# HB-UNI-SenAct-8-8-RC_V1_0.net
KiCad netlist of a schematic drawn in EAGLE
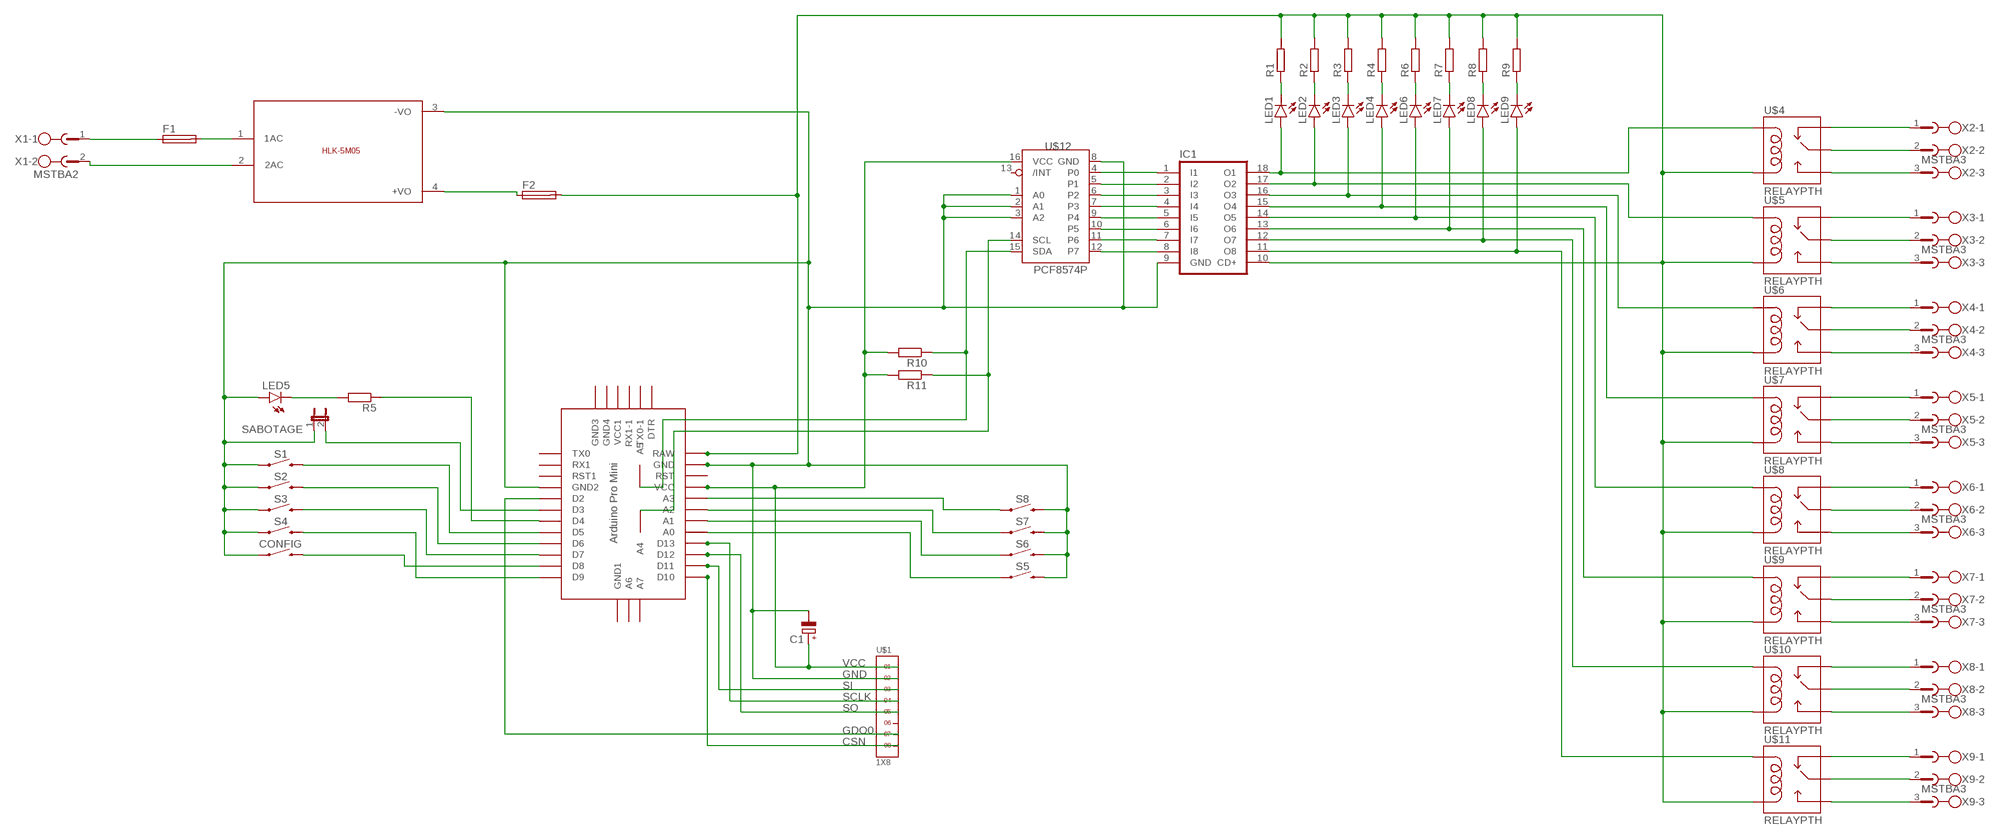
[diagram p0: schematic, sheet 1]

(export (version "E")
  (design (tool "Eeschema 10.0.6"))
  (components
    (comp (ref "C1")
      (value "CPOL-EUE2.5-5")
      (footprint "eagle-import:E2,5-5")
      (libsource (lib "eagle-import") (part "CPOL-EUE2.5-5"))
    )
    (comp (ref "CONFIG")
      (value "MOMENTARY-SWITCH-SPST-PTH-6.0MM-KIT")
      (footprint "eagle-import:TACTILE_SWITCH_PTH_6.0MM_KIT")
      (libsource (lib "eagle-import") (part "MOMENTARY-SWITCH-SPST-PTH-6.0MM-KIT"))
    )
    (comp (ref "F1")
      (value "SH22,5A")
      (footprint "eagle-import:SH22,5A")
      (fields (field (name "MPN") "0031.7701.11"))
      (libsource (lib "eagle-import") (part "SH22,5A"))
    )
    (comp (ref "F2")
      (value "SH22,5A")
      (footprint "eagle-import:SH22,5A")
      (fields (field (name "MPN") "0031.7701.11"))
      (libsource (lib "eagle-import") (part "SH22,5A"))
    )
    (comp (ref "IC1")
      (value "ULN2803A")
      (footprint "eagle-import:DIL18")
      (libsource (lib "eagle-import") (part "ULN2803A"))
    )
    (comp (ref "LED1")
      (value "LED3MM")
      (footprint "eagle-import:LED3MM")
      (libsource (lib "eagle-import") (part "LED3MM"))
    )
    (comp (ref "LED2")
      (value "LED3MM")
      (footprint "eagle-import:LED3MM")
      (libsource (lib "eagle-import") (part "LED3MM"))
    )
    (comp (ref "LED3")
      (value "LED3MM")
      (footprint "eagle-import:LED3MM")
      (libsource (lib "eagle-import") (part "LED3MM"))
    )
    (comp (ref "LED4")
      (value "LED3MM")
      (footprint "eagle-import:LED3MM")
      (libsource (lib "eagle-import") (part "LED3MM"))
    )
    (comp (ref "LED5")
      (value "LED3MM")
      (footprint "eagle-import:LED3MM")
      (libsource (lib "eagle-import") (part "LED3MM"))
    )
    (comp (ref "LED6")
      (value "LED3MM")
      (footprint "eagle-import:LED3MM")
      (libsource (lib "eagle-import") (part "LED3MM"))
    )
    (comp (ref "LED7")
      (value "LED3MM")
      (footprint "eagle-import:LED3MM")
      (libsource (lib "eagle-import") (part "LED3MM"))
    )
    (comp (ref "LED8")
      (value "LED3MM")
      (footprint "eagle-import:LED3MM")
      (libsource (lib "eagle-import") (part "LED3MM"))
    )
    (comp (ref "LED9")
      (value "LED3MM")
      (footprint "eagle-import:LED3MM")
      (libsource (lib "eagle-import") (part "LED3MM"))
    )
    (comp (ref "R1")
      (value "R-EU_0309/10")
      (footprint "eagle-import:0309_10")
      (libsource (lib "eagle-import") (part "R-EU_0309/10"))
    )
    (comp (ref "R2")
      (value "R-EU_0309/10")
      (footprint "eagle-import:0309_10")
      (libsource (lib "eagle-import") (part "R-EU_0309/10"))
    )
    (comp (ref "R3")
      (value "R-EU_0309/10")
      (footprint "eagle-import:0309_10")
      (libsource (lib "eagle-import") (part "R-EU_0309/10"))
    )
    (comp (ref "R4")
      (value "R-EU_0309/10")
      (footprint "eagle-import:0309_10")
      (libsource (lib "eagle-import") (part "R-EU_0309/10"))
    )
    (comp (ref "R5")
      (value "R-EU_0309/10")
      (footprint "eagle-import:0309_10")
      (libsource (lib "eagle-import") (part "R-EU_0309/10"))
    )
    (comp (ref "R6")
      (value "R-EU_0309/10")
      (footprint "eagle-import:0309_10")
      (libsource (lib "eagle-import") (part "R-EU_0309/10"))
    )
    (comp (ref "R7")
      (value "R-EU_0309/10")
      (footprint "eagle-import:0309_10")
      (libsource (lib "eagle-import") (part "R-EU_0309/10"))
    )
    (comp (ref "R8")
      (value "R-EU_0309/10")
      (footprint "eagle-import:0309_10")
      (libsource (lib "eagle-import") (part "R-EU_0309/10"))
    )
    (comp (ref "R9")
      (value "R-EU_0309/10")
      (footprint "eagle-import:0309_10")
      (libsource (lib "eagle-import") (part "R-EU_0309/10"))
    )
    (comp (ref "R10")
      (value "R-EU_0309/10")
      (footprint "eagle-import:0309_10")
      (libsource (lib "eagle-import") (part "R-EU_0309/10"))
    )
    (comp (ref "R11")
      (value "R-EU_0309/10")
      (footprint "eagle-import:0309_10")
      (libsource (lib "eagle-import") (part "R-EU_0309/10"))
    )
    (comp (ref "S1")
      (value "MOMENTARY-SWITCH-SPST-PTH-6.0MM")
      (footprint "eagle-import:TACTILE_SWITCH_PTH_6.0MM")
      (libsource (lib "eagle-import") (part "MOMENTARY-SWITCH-SPST-PTH-6.0MM"))
    )
    (comp (ref "S2")
      (value "MOMENTARY-SWITCH-SPST-PTH-6.0MM-KIT")
      (footprint "eagle-import:TACTILE_SWITCH_PTH_6.0MM_KIT")
      (libsource (lib "eagle-import") (part "MOMENTARY-SWITCH-SPST-PTH-6.0MM-KIT"))
    )
    (comp (ref "S3")
      (value "MOMENTARY-SWITCH-SPST-PTH-6.0MM-KIT")
      (footprint "eagle-import:TACTILE_SWITCH_PTH_6.0MM_KIT")
      (libsource (lib "eagle-import") (part "MOMENTARY-SWITCH-SPST-PTH-6.0MM-KIT"))
    )
    (comp (ref "S4")
      (value "MOMENTARY-SWITCH-SPST-PTH-6.0MM-KIT")
      (footprint "eagle-import:TACTILE_SWITCH_PTH_6.0MM_KIT")
      (libsource (lib "eagle-import") (part "MOMENTARY-SWITCH-SPST-PTH-6.0MM-KIT"))
    )
    (comp (ref "S5")
      (value "MOMENTARY-SWITCH-SPST-PTH-6.0MM-KIT")
      (footprint "eagle-import:TACTILE_SWITCH_PTH_6.0MM_KIT")
      (libsource (lib "eagle-import") (part "MOMENTARY-SWITCH-SPST-PTH-6.0MM-KIT"))
    )
    (comp (ref "S6")
      (value "MOMENTARY-SWITCH-SPST-PTH-6.0MM-KIT")
      (footprint "eagle-import:TACTILE_SWITCH_PTH_6.0MM_KIT")
      (libsource (lib "eagle-import") (part "MOMENTARY-SWITCH-SPST-PTH-6.0MM-KIT"))
    )
    (comp (ref "S7")
      (value "MOMENTARY-SWITCH-SPST-PTH-6.0MM-KIT")
      (footprint "eagle-import:TACTILE_SWITCH_PTH_6.0MM_KIT")
      (libsource (lib "eagle-import") (part "MOMENTARY-SWITCH-SPST-PTH-6.0MM-KIT"))
    )
    (comp (ref "S8")
      (value "MOMENTARY-SWITCH-SPST-PTH-6.0MM-KIT")
      (footprint "eagle-import:TACTILE_SWITCH_PTH_6.0MM_KIT")
      (libsource (lib "eagle-import") (part "MOMENTARY-SWITCH-SPST-PTH-6.0MM-KIT"))
    )
    (comp (ref "SABOTAGE")
      (value "JP1E")
      (footprint "eagle-import:JP1")
      (libsource (lib "eagle-import") (part "JP1E"))
    )
    (comp (ref "U$1")
      (value "1X8")
      (footprint "eagle-import:1X8")
      (libsource (lib "eagle-import") (part "1X8"))
    )
    (comp (ref "U$2")
      (value "ABK-PRO-MINI")
      (footprint "eagle-import:ABK-PRO-MINI")
      (libsource (lib "eagle-import") (part "ABK-PRO-MINI"))
    )
    (comp (ref "U$3")
      (value "5VDC/5W")
      (footprint "eagle-import:HLK-5M05")
      (libsource (lib "eagle-import") (part "HLK-5M05"))
    )
    (comp (ref "U$4")
      (value "RELAYPTH")
      (footprint "eagle-import:SRD-05VDC-SL-C")
      (libsource (lib "eagle-import") (part "RELAYPTH"))
    )
    (comp (ref "U$5")
      (value "RELAYPTH")
      (footprint "eagle-import:SRD-05VDC-SL-C")
      (libsource (lib "eagle-import") (part "RELAYPTH"))
    )
    (comp (ref "U$6")
      (value "RELAYPTH")
      (footprint "eagle-import:SRD-05VDC-SL-C")
      (libsource (lib "eagle-import") (part "RELAYPTH"))
    )
    (comp (ref "U$7")
      (value "RELAYPTH")
      (footprint "eagle-import:SRD-05VDC-SL-C")
      (libsource (lib "eagle-import") (part "RELAYPTH"))
    )
    (comp (ref "U$8")
      (value "RELAYPTH")
      (footprint "eagle-import:SRD-05VDC-SL-C")
      (libsource (lib "eagle-import") (part "RELAYPTH"))
    )
    (comp (ref "U$9")
      (value "RELAYPTH")
      (footprint "eagle-import:SRD-05VDC-SL-C")
      (libsource (lib "eagle-import") (part "RELAYPTH"))
    )
    (comp (ref "U$10")
      (value "RELAYPTH")
      (footprint "eagle-import:SRD-05VDC-SL-C")
      (libsource (lib "eagle-import") (part "RELAYPTH"))
    )
    (comp (ref "U$11")
      (value "RELAYPTH")
      (footprint "eagle-import:SRD-05VDC-SL-C")
      (libsource (lib "eagle-import") (part "RELAYPTH"))
    )
    (comp (ref "U$12")
      (value "PCF8574P")
      (footprint "eagle-import:DIL16")
      (libsource (lib "eagle-import") (part "PCF8574P"))
    )
    (comp (ref "X1")
      (value "MSTBA2")
      (footprint "eagle-import:MSTBA2")
      (fields (field (name "MF") "FARNELL") (field (name "MPN") "1757242"))
      (libsource (lib "eagle-import") (part "MSTBA2"))
    )
    (comp (ref "X2")
      (value "MSTBA3")
      (footprint "eagle-import:MSTBA3")
      (fields (field (name "MF") "FARNELL") (field (name "MPN") "1757255"))
      (libsource (lib "eagle-import") (part "MSTBA3"))
    )
    (comp (ref "X3")
      (value "MSTBA3")
      (footprint "eagle-import:MSTBA3")
      (fields (field (name "MF") "FARNELL") (field (name "MPN") "1757255"))
      (libsource (lib "eagle-import") (part "MSTBA3"))
    )
    (comp (ref "X4")
      (value "MSTBA3")
      (footprint "eagle-import:MSTBA3")
      (fields (field (name "MF") "FARNELL") (field (name "MPN") "1757255"))
      (libsource (lib "eagle-import") (part "MSTBA3"))
    )
    (comp (ref "X5")
      (value "MSTBA3")
      (footprint "eagle-import:MSTBA3")
      (fields (field (name "MF") "FARNELL") (field (name "MPN") "1757255"))
      (libsource (lib "eagle-import") (part "MSTBA3"))
    )
    (comp (ref "X6")
      (value "MSTBA3")
      (footprint "eagle-import:MSTBA3")
      (fields (field (name "MF") "FARNELL") (field (name "MPN") "1757255"))
      (libsource (lib "eagle-import") (part "MSTBA3"))
    )
    (comp (ref "X7")
      (value "MSTBA3")
      (footprint "eagle-import:MSTBA3")
      (fields (field (name "MF") "FARNELL") (field (name "MPN") "1757255"))
      (libsource (lib "eagle-import") (part "MSTBA3"))
    )
    (comp (ref "X8")
      (value "MSTBA3")
      (footprint "eagle-import:MSTBA3")
      (fields (field (name "MF") "FARNELL") (field (name "MPN") "1757255"))
      (libsource (lib "eagle-import") (part "MSTBA3"))
    )
    (comp (ref "X9")
      (value "MSTBA3")
      (footprint "eagle-import:MSTBA3")
      (fields (field (name "MF") "FARNELL") (field (name "MPN") "1757255"))
      (libsource (lib "eagle-import") (part "MSTBA3"))
    )
  )
  (nets
    (net (code "1") (name "/CSN") (class "Default")
      (node (ref "U$1") (pin "8") (pinfunction "8_8") (pintype "bidirectional"))
      (node (ref "U$2") (pin "D10") (pinfunction "D10_D10") (pintype "bidirectional"))
    )
    (net (code "2") (name "/GDO0") (class "Default")
      (node (ref "U$1") (pin "7") (pinfunction "7_7") (pintype "bidirectional"))
      (node (ref "U$2") (pin "D2") (pinfunction "D2_D2") (pintype "bidirectional"))
    )
    (net (code "3") (name "/GND") (class "Default")
      (node (ref "C1") (pin "-") (pinfunction "-_-") (pintype "passive"))
      (node (ref "CONFIG") (pin "1") (pinfunction "1_1") (pintype "passive"))
      (node (ref "IC1") (pin "9") (pinfunction "GND_9") (pintype "power_in"))
      (node (ref "LED5") (pin "A") (pinfunction "A_A") (pintype "passive"))
      (node (ref "S1") (pin "1") (pinfunction "1_1") (pintype "passive"))
      (node (ref "S2") (pin "1") (pinfunction "1_1") (pintype "passive"))
      (node (ref "S3") (pin "1") (pinfunction "1_1") (pintype "passive"))
      (node (ref "S4") (pin "1") (pinfunction "1_1") (pintype "passive"))
      (node (ref "S5") (pin "3") (pinfunction "2_3") (pintype "passive"))
      (node (ref "S6") (pin "3") (pinfunction "2_3") (pintype "passive"))
      (node (ref "S7") (pin "3") (pinfunction "2_3") (pintype "passive"))
      (node (ref "S8") (pin "3") (pinfunction "2_3") (pintype "passive"))
      (node (ref "SABOTAGE") (pin "1") (pinfunction "1_1") (pintype "passive"))
      (node (ref "U$1") (pin "2") (pinfunction "2_2") (pintype "bidirectional"))
      (node (ref "U$12") (pin "1") (pinfunction "A0_1") (pintype "input"))
      (node (ref "U$12") (pin "2") (pinfunction "A1_2") (pintype "input"))
      (node (ref "U$12") (pin "3") (pinfunction "A2_3") (pintype "input"))
      (node (ref "U$12") (pin "8") (pinfunction "GND_8") (pintype "power_in"))
      (node (ref "U$2") (pin "GND") (pinfunction "GND_GND") (pintype "bidirectional"))
      (node (ref "U$2") (pin "GND1") (pinfunction "GND2_GND1") (pintype "bidirectional"))
      (node (ref "U$3") (pin "3") (pinfunction "-VO_3") (pintype "bidirectional"))
    )
    (net (code "4") (name "/SCLK") (class "Default")
      (node (ref "U$1") (pin "4") (pinfunction "4_4") (pintype "bidirectional"))
      (node (ref "U$2") (pin "D13") (pinfunction "D13_D13") (pintype "bidirectional"))
    )
    (net (code "5") (name "/SI") (class "Default")
      (node (ref "U$1") (pin "3") (pinfunction "3_3") (pintype "bidirectional"))
      (node (ref "U$2") (pin "D11") (pinfunction "D11_D11") (pintype "bidirectional"))
    )
    (net (code "6") (name "/SO") (class "Default")
      (node (ref "U$1") (pin "5") (pinfunction "5_5") (pintype "bidirectional"))
      (node (ref "U$2") (pin "D12") (pinfunction "D12_D12") (pintype "bidirectional"))
    )
    (net (code "7") (name "/VCC") (class "Default")
      (node (ref "C1") (pin "+") (pinfunction "+_+") (pintype "passive"))
      (node (ref "R10") (pin "2") (pinfunction "2_2") (pintype "passive"))
      (node (ref "R11") (pin "2") (pinfunction "2_2") (pintype "passive"))
      (node (ref "U$1") (pin "1") (pinfunction "1_1") (pintype "bidirectional"))
      (node (ref "U$12") (pin "16") (pinfunction "VCC_16") (pintype "power_in"))
      (node (ref "U$2") (pin "VCC") (pinfunction "VCC_VCC") (pintype "bidirectional"))
    )
    (net (code "8") (name "Net-(CONFIG-2)") (class "Default")
      (node (ref "CONFIG") (pin "3") (pinfunction "2_3") (pintype "passive"))
      (node (ref "U$2") (pin "D8") (pinfunction "D8_D8") (pintype "bidirectional"))
    )
    (net (code "9") (name "Net-(F1-Pad1)") (class "Default")
      (node (ref "F1") (pin "1") (pinfunction "1_1") (pintype "passive"))
      (node (ref "X1") (pin "1") (pinfunction "1_1") (pintype "passive"))
    )
    (net (code "10") (name "Net-(IC1-CD+)") (class "Default")
      (node (ref "F2") (pin "2") (pinfunction "2_2") (pintype "passive"))
      (node (ref "IC1") (pin "10") (pinfunction "CD+_10") (pintype "passive"))
      (node (ref "R1") (pin "2") (pinfunction "2_2") (pintype "passive"))
      (node (ref "R2") (pin "2") (pinfunction "2_2") (pintype "passive"))
      (node (ref "R3") (pin "2") (pinfunction "2_2") (pintype "passive"))
      (node (ref "R4") (pin "2") (pinfunction "2_2") (pintype "passive"))
      (node (ref "R6") (pin "2") (pinfunction "2_2") (pintype "passive"))
      (node (ref "R7") (pin "2") (pinfunction "2_2") (pintype "passive"))
      (node (ref "R8") (pin "2") (pinfunction "2_2") (pintype "passive"))
      (node (ref "R9") (pin "2") (pinfunction "2_2") (pintype "passive"))
      (node (ref "U$10") (pin "COIL0") (pinfunction "COIL0_COIL0") (pintype "bidirectional"))
      (node (ref "U$11") (pin "COIL0") (pinfunction "COIL0_COIL0") (pintype "bidirectional"))
      (node (ref "U$2") (pin "RAW") (pinfunction "RAW_RAW") (pintype "bidirectional"))
      (node (ref "U$4") (pin "COIL0") (pinfunction "COIL0_COIL0") (pintype "bidirectional"))
      (node (ref "U$5") (pin "COIL0") (pinfunction "COIL0_COIL0") (pintype "bidirectional"))
      (node (ref "U$6") (pin "COIL0") (pinfunction "COIL0_COIL0") (pintype "bidirectional"))
      (node (ref "U$7") (pin "COIL0") (pinfunction "COIL0_COIL0") (pintype "bidirectional"))
      (node (ref "U$8") (pin "COIL0") (pinfunction "COIL0_COIL0") (pintype "bidirectional"))
      (node (ref "U$9") (pin "COIL0") (pinfunction "COIL0_COIL0") (pintype "bidirectional"))
    )
    (net (code "11") (name "Net-(IC1-I1)") (class "Default")
      (node (ref "IC1") (pin "1") (pinfunction "I1_1") (pintype "input"))
      (node (ref "U$12") (pin "4") (pinfunction "P0_4") (pintype "bidirectional"))
    )
    (net (code "12") (name "Net-(IC1-I2)") (class "Default")
      (node (ref "IC1") (pin "2") (pinfunction "I2_2") (pintype "input"))
      (node (ref "U$12") (pin "5") (pinfunction "P1_5") (pintype "bidirectional"))
    )
    (net (code "13") (name "Net-(IC1-I3)") (class "Default")
      (node (ref "IC1") (pin "3") (pinfunction "I3_3") (pintype "input"))
      (node (ref "U$12") (pin "6") (pinfunction "P2_6") (pintype "bidirectional"))
    )
    (net (code "14") (name "Net-(IC1-I4)") (class "Default")
      (node (ref "IC1") (pin "4") (pinfunction "I4_4") (pintype "input"))
      (node (ref "U$12") (pin "7") (pinfunction "P3_7") (pintype "bidirectional"))
    )
    (net (code "15") (name "Net-(IC1-I5)") (class "Default")
      (node (ref "IC1") (pin "5") (pinfunction "I5_5") (pintype "input"))
      (node (ref "U$12") (pin "9") (pinfunction "P4_9") (pintype "bidirectional"))
    )
    (net (code "16") (name "Net-(IC1-I6)") (class "Default")
      (node (ref "IC1") (pin "6") (pinfunction "I6_6") (pintype "input"))
      (node (ref "U$12") (pin "10") (pinfunction "P5_10") (pintype "bidirectional"))
    )
    (net (code "17") (name "Net-(IC1-I7)") (class "Default")
      (node (ref "IC1") (pin "7") (pinfunction "I7_7") (pintype "input"))
      (node (ref "U$12") (pin "11") (pinfunction "P6_11") (pintype "bidirectional"))
    )
    (net (code "18") (name "Net-(IC1-I8)") (class "Default")
      (node (ref "IC1") (pin "8") (pinfunction "I8_8") (pintype "input"))
      (node (ref "U$12") (pin "12") (pinfunction "P7_12") (pintype "bidirectional"))
    )
    (net (code "19") (name "Net-(IC1-O1)") (class "Default")
      (node (ref "IC1") (pin "18") (pinfunction "O1_18") (pintype "open_collector"))
      (node (ref "LED1") (pin "A") (pinfunction "A_A") (pintype "passive"))
      (node (ref "U$4") (pin "COIL1") (pinfunction "COIL1_COIL1") (pintype "bidirectional"))
    )
    (net (code "20") (name "Net-(IC1-O2)") (class "Default")
      (node (ref "IC1") (pin "17") (pinfunction "O2_17") (pintype "open_collector"))
      (node (ref "LED2") (pin "A") (pinfunction "A_A") (pintype "passive"))
      (node (ref "U$5") (pin "COIL1") (pinfunction "COIL1_COIL1") (pintype "bidirectional"))
    )
    (net (code "21") (name "Net-(IC1-O3)") (class "Default")
      (node (ref "IC1") (pin "16") (pinfunction "O3_16") (pintype "open_collector"))
      (node (ref "LED3") (pin "A") (pinfunction "A_A") (pintype "passive"))
      (node (ref "U$6") (pin "COIL1") (pinfunction "COIL1_COIL1") (pintype "bidirectional"))
    )
    (net (code "22") (name "Net-(IC1-O4)") (class "Default")
      (node (ref "IC1") (pin "15") (pinfunction "O4_15") (pintype "open_collector"))
      (node (ref "LED4") (pin "A") (pinfunction "A_A") (pintype "passive"))
      (node (ref "U$7") (pin "COIL1") (pinfunction "COIL1_COIL1") (pintype "bidirectional"))
    )
    (net (code "23") (name "Net-(IC1-O5)") (class "Default")
      (node (ref "IC1") (pin "14") (pinfunction "O5_14") (pintype "open_collector"))
      (node (ref "LED6") (pin "A") (pinfunction "A_A") (pintype "passive"))
      (node (ref "U$8") (pin "COIL1") (pinfunction "COIL1_COIL1") (pintype "bidirectional"))
    )
    (net (code "24") (name "Net-(IC1-O6)") (class "Default")
      (node (ref "IC1") (pin "13") (pinfunction "O6_13") (pintype "open_collector"))
      (node (ref "LED7") (pin "A") (pinfunction "A_A") (pintype "passive"))
      (node (ref "U$9") (pin "COIL1") (pinfunction "COIL1_COIL1") (pintype "bidirectional"))
    )
    (net (code "25") (name "Net-(IC1-O7)") (class "Default")
      (node (ref "IC1") (pin "12") (pinfunction "O7_12") (pintype "open_collector"))
      (node (ref "LED8") (pin "A") (pinfunction "A_A") (pintype "passive"))
      (node (ref "U$10") (pin "COIL1") (pinfunction "COIL1_COIL1") (pintype "bidirectional"))
    )
    (net (code "26") (name "Net-(IC1-O8)") (class "Default")
      (node (ref "IC1") (pin "11") (pinfunction "O8_11") (pintype "open_collector"))
      (node (ref "LED9") (pin "A") (pinfunction "A_A") (pintype "passive"))
      (node (ref "U$11") (pin "COIL1") (pinfunction "COIL1_COIL1") (pintype "bidirectional"))
    )
    (net (code "27") (name "Net-(LED1-C)") (class "Default")
      (node (ref "LED1") (pin "K") (pinfunction "C_K") (pintype "passive"))
      (node (ref "R1") (pin "1") (pinfunction "1_1") (pintype "passive"))
    )
    (net (code "28") (name "Net-(LED2-C)") (class "Default")
      (node (ref "LED2") (pin "K") (pinfunction "C_K") (pintype "passive"))
      (node (ref "R2") (pin "1") (pinfunction "1_1") (pintype "passive"))
    )
    (net (code "29") (name "Net-(LED3-C)") (class "Default")
      (node (ref "LED3") (pin "K") (pinfunction "C_K") (pintype "passive"))
      (node (ref "R3") (pin "1") (pinfunction "1_1") (pintype "passive"))
    )
    (net (code "30") (name "Net-(LED4-C)") (class "Default")
      (node (ref "LED4") (pin "K") (pinfunction "C_K") (pintype "passive"))
      (node (ref "R4") (pin "1") (pinfunction "1_1") (pintype "passive"))
    )
    (net (code "31") (name "Net-(LED5-C)") (class "Default")
      (node (ref "LED5") (pin "K") (pinfunction "C_K") (pintype "passive"))
      (node (ref "R5") (pin "2") (pinfunction "2_2") (pintype "passive"))
    )
    (net (code "32") (name "Net-(LED6-C)") (class "Default")
      (node (ref "LED6") (pin "K") (pinfunction "C_K") (pintype "passive"))
      (node (ref "R6") (pin "1") (pinfunction "1_1") (pintype "passive"))
    )
    (net (code "33") (name "Net-(LED7-C)") (class "Default")
      (node (ref "LED7") (pin "K") (pinfunction "C_K") (pintype "passive"))
      (node (ref "R7") (pin "1") (pinfunction "1_1") (pintype "passive"))
    )
    (net (code "34") (name "Net-(LED8-C)") (class "Default")
      (node (ref "LED8") (pin "K") (pinfunction "C_K") (pintype "passive"))
      (node (ref "R8") (pin "1") (pinfunction "1_1") (pintype "passive"))
    )
    (net (code "35") (name "Net-(LED9-C)") (class "Default")
      (node (ref "LED9") (pin "K") (pinfunction "C_K") (pintype "passive"))
      (node (ref "R9") (pin "1") (pinfunction "1_1") (pintype "passive"))
    )
    (net (code "36") (name "Net-(R5-Pad1)") (class "Default")
      (node (ref "R5") (pin "1") (pinfunction "1_1") (pintype "passive"))
      (node (ref "U$2") (pin "D4") (pinfunction "D4_D4") (pintype "bidirectional"))
    )
    (net (code "37") (name "Net-(S1-2)") (class "Default")
      (node (ref "S1") (pin "3") (pinfunction "2_3") (pintype "passive"))
      (node (ref "U$2") (pin "D5") (pinfunction "D5_D5") (pintype "bidirectional"))
    )
    (net (code "38") (name "Net-(S2-2)") (class "Default")
      (node (ref "S2") (pin "3") (pinfunction "2_3") (pintype "passive"))
      (node (ref "U$2") (pin "D6") (pinfunction "D6_D6") (pintype "bidirectional"))
    )
    (net (code "39") (name "Net-(S3-2)") (class "Default")
      (node (ref "S3") (pin "3") (pinfunction "2_3") (pintype "passive"))
      (node (ref "U$2") (pin "D7") (pinfunction "D7_D7") (pintype "bidirectional"))
    )
    (net (code "40") (name "Net-(S4-2)") (class "Default")
      (node (ref "S4") (pin "3") (pinfunction "2_3") (pintype "passive"))
      (node (ref "U$2") (pin "D9") (pinfunction "D9_D9") (pintype "bidirectional"))
    )
    (net (code "41") (name "Net-(S5-Pad1)") (class "Default")
      (node (ref "S5") (pin "1") (pinfunction "1_1") (pintype "passive"))
      (node (ref "U$2") (pin "A0") (pinfunction "A0_A0") (pintype "bidirectional"))
    )
    (net (code "42") (name "Net-(S6-Pad1)") (class "Default")
      (node (ref "S6") (pin "1") (pinfunction "1_1") (pintype "passive"))
      (node (ref "U$2") (pin "A1") (pinfunction "A1_A1") (pintype "bidirectional"))
    )
    (net (code "43") (name "Net-(S7-Pad1)") (class "Default")
      (node (ref "S7") (pin "1") (pinfunction "1_1") (pintype "passive"))
      (node (ref "U$2") (pin "A2") (pinfunction "A2_A2") (pintype "bidirectional"))
    )
    (net (code "44") (name "Net-(S8-Pad1)") (class "Default")
      (node (ref "S8") (pin "1") (pinfunction "1_1") (pintype "passive"))
      (node (ref "U$2") (pin "A3") (pinfunction "A3_A3") (pintype "bidirectional"))
    )
    (net (code "45") (name "Net-(SABOTAGE-Pad2)") (class "Default")
      (node (ref "SABOTAGE") (pin "2") (pinfunction "2_2") (pintype "passive"))
      (node (ref "U$2") (pin "D3") (pinfunction "D3_D3") (pintype "bidirectional"))
    )
    (net (code "46") (name "Net-(U$3-+VO)") (class "Default")
      (node (ref "F2") (pin "1") (pinfunction "1_1") (pintype "passive"))
      (node (ref "U$3") (pin "4") (pinfunction "+VO_4") (pintype "bidirectional"))
    )
    (net (code "47") (name "Net-(U$3-1AC)") (class "Default")
      (node (ref "F1") (pin "2") (pinfunction "2_2") (pintype "passive"))
      (node (ref "U$3") (pin "1") (pinfunction "1AC_1") (pintype "bidirectional"))
    )
    (net (code "48") (name "Net-(U$3-2AC)") (class "Default")
      (node (ref "U$3") (pin "2") (pinfunction "2AC_2") (pintype "bidirectional"))
      (node (ref "X1") (pin "2") (pinfunction "1_2") (pintype "passive"))
    )
    (net (code "49") (name "Net-(U$4-SWCLOSE)") (class "Default")
      (node (ref "U$4") (pin "SWCLOSED") (pinfunction "SWCLOSE_SWCLOSED") (pintype "bidirectional"))
      (node (ref "X2") (pin "1") (pinfunction "1_1") (pintype "passive"))
    )
    (net (code "50") (name "Net-(U$5-SWCLOSE)") (class "Default")
      (node (ref "U$5") (pin "SWCLOSED") (pinfunction "SWCLOSE_SWCLOSED") (pintype "bidirectional"))
      (node (ref "X3") (pin "1") (pinfunction "1_1") (pintype "passive"))
    )
    (net (code "51") (name "Net-(U$6-SWCLOSE)") (class "Default")
      (node (ref "U$6") (pin "SWCLOSED") (pinfunction "SWCLOSE_SWCLOSED") (pintype "bidirectional"))
      (node (ref "X4") (pin "1") (pinfunction "1_1") (pintype "passive"))
    )
    (net (code "52") (name "Net-(U$7-SWCLOSE)") (class "Default")
      (node (ref "U$7") (pin "SWCLOSED") (pinfunction "SWCLOSE_SWCLOSED") (pintype "bidirectional"))
      (node (ref "X5") (pin "1") (pinfunction "1_1") (pintype "passive"))
    )
    (net (code "53") (name "Net-(U$8-SWCLOSE)") (class "Default")
      (node (ref "U$8") (pin "SWCLOSED") (pinfunction "SWCLOSE_SWCLOSED") (pintype "bidirectional"))
      (node (ref "X6") (pin "1") (pinfunction "1_1") (pintype "passive"))
    )
    (net (code "54") (name "Net-(U$9-SWCLOSE)") (class "Default")
      (node (ref "U$9") (pin "SWCLOSED") (pinfunction "SWCLOSE_SWCLOSED") (pintype "bidirectional"))
      (node (ref "X7") (pin "1") (pinfunction "1_1") (pintype "passive"))
    )
    (net (code "55") (name "Net-(U$10-SWCLOSE)") (class "Default")
      (node (ref "U$10") (pin "SWCLOSED") (pinfunction "SWCLOSE_SWCLOSED") (pintype "bidirectional"))
      (node (ref "X8") (pin "1") (pinfunction "1_1") (pintype "passive"))
    )
    (net (code "56") (name "Net-(U$11-SWCLOSE)") (class "Default")
      (node (ref "U$11") (pin "SWCLOSED") (pinfunction "SWCLOSE_SWCLOSED") (pintype "bidirectional"))
      (node (ref "X9") (pin "1") (pinfunction "1_1") (pintype "passive"))
    )
    (net (code "57") (name "Net-(U$12-SCL)") (class "Default")
      (node (ref "R11") (pin "1") (pinfunction "1_1") (pintype "passive"))
      (node (ref "U$12") (pin "14") (pinfunction "SCL_14") (pintype "input"))
      (node (ref "U$2") (pin "A4") (pinfunction "A4_A4") (pintype "bidirectional"))
    )
    (net (code "58") (name "Net-(U$12-SDA)") (class "Default")
      (node (ref "R10") (pin "1") (pinfunction "1_1") (pintype "passive"))
      (node (ref "U$12") (pin "15") (pinfunction "SDA_15") (pintype "bidirectional"))
      (node (ref "U$2") (pin "A5") (pinfunction "A5_A5") (pintype "bidirectional"))
    )
    (net (code "59") (name "Net-(X2B-1)") (class "Default")
      (node (ref "U$4") (pin "SWCOMMON") (pinfunction "SWCOMMON_SWCOMMON") (pintype "bidirectional"))
      (node (ref "X2") (pin "2") (pinfunction "1_2") (pintype "passive"))
    )
    (net (code "60") (name "Net-(X2C-1)") (class "Default")
      (node (ref "U$4") (pin "SWOPEN") (pinfunction "SWOPEN_SWOPEN") (pintype "bidirectional"))
      (node (ref "X2") (pin "3") (pinfunction "1_3") (pintype "passive"))
    )
    (net (code "61") (name "Net-(X3B-1)") (class "Default")
      (node (ref "U$5") (pin "SWCOMMON") (pinfunction "SWCOMMON_SWCOMMON") (pintype "bidirectional"))
      (node (ref "X3") (pin "2") (pinfunction "1_2") (pintype "passive"))
    )
    (net (code "62") (name "Net-(X3C-1)") (class "Default")
      (node (ref "U$5") (pin "SWOPEN") (pinfunction "SWOPEN_SWOPEN") (pintype "bidirectional"))
      (node (ref "X3") (pin "3") (pinfunction "1_3") (pintype "passive"))
    )
    (net (code "63") (name "Net-(X4B-1)") (class "Default")
      (node (ref "U$6") (pin "SWCOMMON") (pinfunction "SWCOMMON_SWCOMMON") (pintype "bidirectional"))
      (node (ref "X4") (pin "2") (pinfunction "1_2") (pintype "passive"))
    )
    (net (code "64") (name "Net-(X4C-1)") (class "Default")
      (node (ref "U$6") (pin "SWOPEN") (pinfunction "SWOPEN_SWOPEN") (pintype "bidirectional"))
      (node (ref "X4") (pin "3") (pinfunction "1_3") (pintype "passive"))
    )
    (net (code "65") (name "Net-(X5B-1)") (class "Default")
      (node (ref "U$7") (pin "SWCOMMON") (pinfunction "SWCOMMON_SWCOMMON") (pintype "bidirectional"))
      (node (ref "X5") (pin "2") (pinfunction "1_2") (pintype "passive"))
    )
    (net (code "66") (name "Net-(X5C-1)") (class "Default")
      (node (ref "U$7") (pin "SWOPEN") (pinfunction "SWOPEN_SWOPEN") (pintype "bidirectional"))
      (node (ref "X5") (pin "3") (pinfunction "1_3") (pintype "passive"))
    )
    (net (code "67") (name "Net-(X6B-1)") (class "Default")
      (node (ref "U$8") (pin "SWCOMMON") (pinfunction "SWCOMMON_SWCOMMON") (pintype "bidirectional"))
      (node (ref "X6") (pin "2") (pinfunction "1_2") (pintype "passive"))
    )
    (net (code "68") (name "Net-(X6C-1)") (class "Default")
      (node (ref "U$8") (pin "SWOPEN") (pinfunction "SWOPEN_SWOPEN") (pintype "bidirectional"))
      (node (ref "X6") (pin "3") (pinfunction "1_3") (pintype "passive"))
    )
    (net (code "69") (name "Net-(X7B-1)") (class "Default")
      (node (ref "U$9") (pin "SWCOMMON") (pinfunction "SWCOMMON_SWCOMMON") (pintype "bidirectional"))
      (node (ref "X7") (pin "2") (pinfunction "1_2") (pintype "passive"))
    )
    (net (code "70") (name "Net-(X7C-1)") (class "Default")
      (node (ref "U$9") (pin "SWOPEN") (pinfunction "SWOPEN_SWOPEN") (pintype "bidirectional"))
      (node (ref "X7") (pin "3") (pinfunction "1_3") (pintype "passive"))
    )
    (net (code "71") (name "Net-(X8B-1)") (class "Default")
      (node (ref "U$10") (pin "SWCOMMON") (pinfunction "SWCOMMON_SWCOMMON") (pintype "bidirectional"))
      (node (ref "X8") (pin "2") (pinfunction "1_2") (pintype "passive"))
    )
    (net (code "72") (name "Net-(X8C-1)") (class "Default")
      (node (ref "U$10") (pin "SWOPEN") (pinfunction "SWOPEN_SWOPEN") (pintype "bidirectional"))
      (node (ref "X8") (pin "3") (pinfunction "1_3") (pintype "passive"))
    )
    (net (code "73") (name "Net-(X9B-1)") (class "Default")
      (node (ref "U$11") (pin "SWCOMMON") (pinfunction "SWCOMMON_SWCOMMON") (pintype "bidirectional"))
      (node (ref "X9") (pin "2") (pinfunction "1_2") (pintype "passive"))
    )
    (net (code "74") (name "Net-(X9C-1)") (class "Default")
      (node (ref "U$11") (pin "SWOPEN") (pinfunction "SWOPEN_SWOPEN") (pintype "bidirectional"))
      (node (ref "X9") (pin "3") (pinfunction "1_3") (pintype "passive"))
    )
    (net (code "75") (name "unconnected-(U$1-Pad6)") (class "Default")
      (node (ref "U$1") (pin "6") (pinfunction "6_6") (pintype "bidirectional"))
    )
    (net (code "76") (name "unconnected-(U$2-GND1-PadGND4)") (class "Default")
      (node (ref "U$2") (pin "GND4") (pinfunction "GND1_GND4") (pintype "bidirectional"))
    )
    (net (code "77") (name "unconnected-(U$2-GND3-PadGND2)") (class "Default")
      (node (ref "U$2") (pin "GND2") (pinfunction "GND3_GND2") (pintype "bidirectional"))
    )
    (net (code "78") (name "unconnected-(U$2-GND4-PadGND3)") (class "Default")
      (node (ref "U$2") (pin "GND3") (pinfunction "GND4_GND3") (pintype "bidirectional"))
    )
    (net (code "79") (name "unconnected-(U$2-PadA6)") (class "Default")
      (node (ref "U$2") (pin "A6") (pinfunction "A6_A6") (pintype "bidirectional"))
    )
    (net (code "80") (name "unconnected-(U$2-PadA7)") (class "Default")
      (node (ref "U$2") (pin "A7") (pinfunction "A7_A7") (pintype "bidirectional"))
    )
    (net (code "81") (name "unconnected-(U$2-PadDTR)") (class "Default")
      (node (ref "U$2") (pin "DTR") (pinfunction "DTR_DTR") (pintype "bidirectional"))
    )
    (net (code "82") (name "unconnected-(U$2-PadRST)") (class "Default")
      (node (ref "U$2") (pin "RST") (pinfunction "RST_RST") (pintype "bidirectional"))
    )
    (net (code "83") (name "unconnected-(U$2-PadRST1)") (class "Default")
      (node (ref "U$2") (pin "RST1") (pinfunction "RST1_RST1") (pintype "bidirectional"))
    )
    (net (code "84") (name "unconnected-(U$2-PadRX1)") (class "Default")
      (node (ref "U$2") (pin "RX1") (pinfunction "RX1_RX1") (pintype "bidirectional"))
    )
    (net (code "85") (name "unconnected-(U$2-PadRX1-1)") (class "Default")
      (node (ref "U$2") (pin "RX1-1") (pinfunction "RX1-1_RX1-1") (pintype "bidirectional"))
    )
    (net (code "86") (name "unconnected-(U$2-PadTX0)") (class "Default")
      (node (ref "U$2") (pin "TX0") (pinfunction "TX0_TX0") (pintype "bidirectional"))
    )
    (net (code "87") (name "unconnected-(U$2-PadTX0-1)") (class "Default")
      (node (ref "U$2") (pin "TX0-1") (pinfunction "TX0-1_TX0-1") (pintype "bidirectional"))
    )
    (net (code "88") (name "unconnected-(U$2-PadVCC1)") (class "Default")
      (node (ref "U$2") (pin "VCC1") (pinfunction "VCC1_VCC1") (pintype "bidirectional"))
    )
    (net (code "89") (name "unconnected-(U$12-{slash}INT-Pad13)") (class "Default")
      (node (ref "U$12") (pin "13") (pinfunction "/INT_13") (pintype "output"))
    )
  )
)
